# BoomOtter.net
KiCad netlist of a schematic drawn in EAGLE
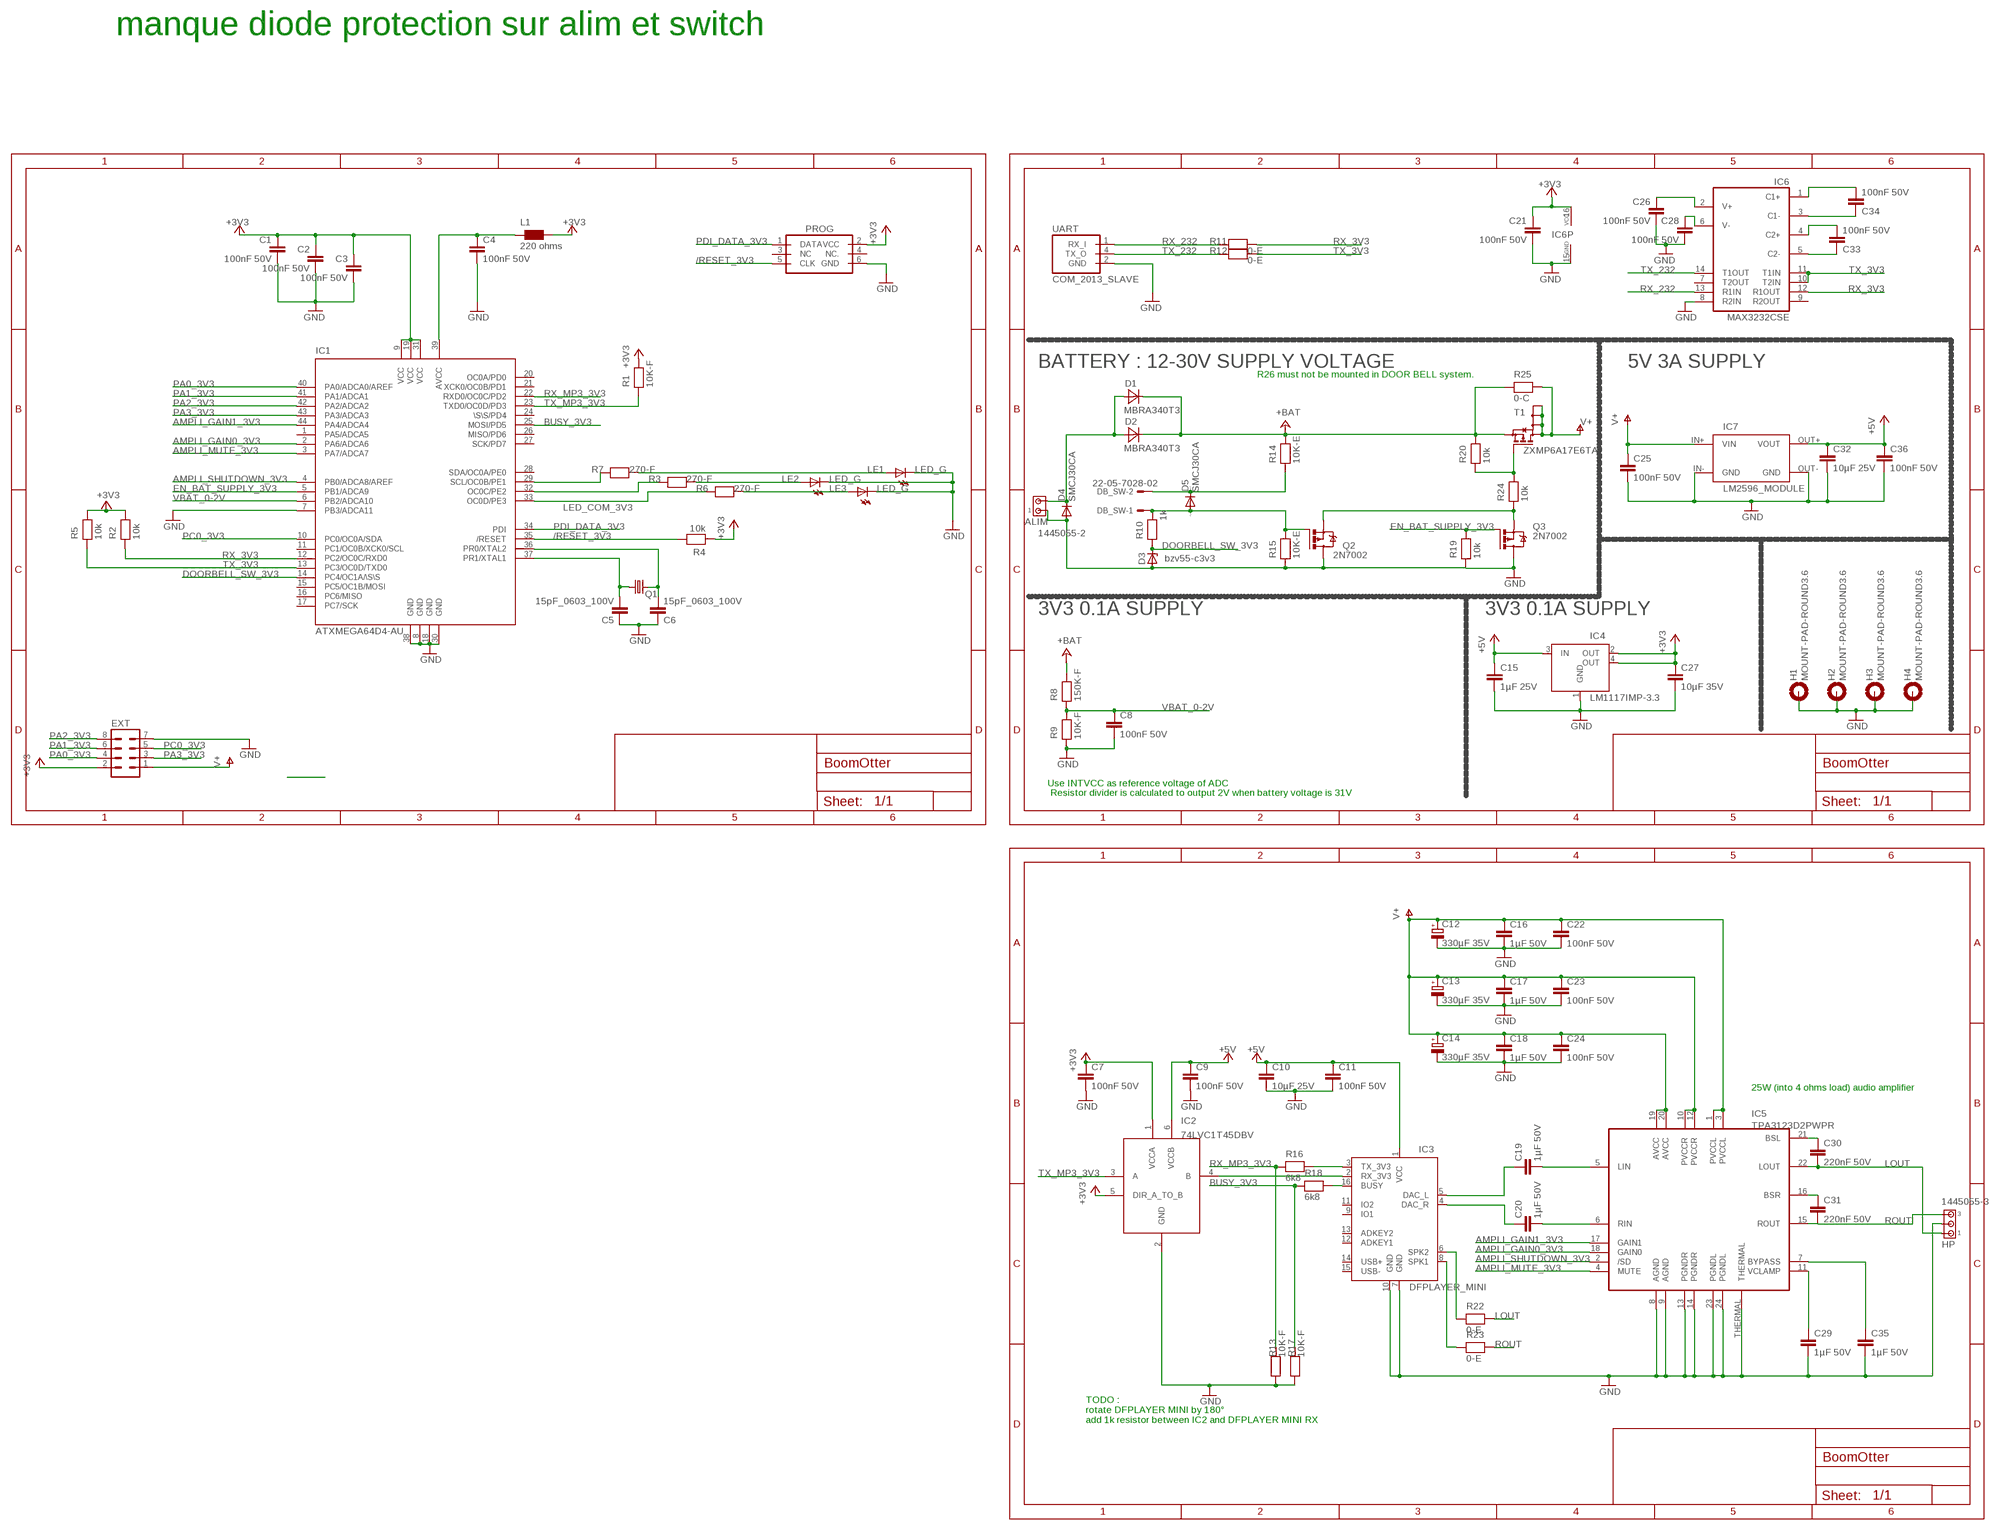
[diagram p0: schematic, sheet 1]

(export (version "E")
  (design (tool "Eeschema 10.0.6"))
  (components
    (comp (ref "ALIM")
      (value "1445055-2")
      (footprint "eagle-import:1445055-2")
      (libsource (lib "eagle-import") (part "1445055-2"))
    )
    (comp (ref "C1")
      (value "100nF 50V")
      (footprint "eagle-import:C0603")
      (libsource (lib "eagle-import") (part "100NF-F"))
    )
    (comp (ref "C2")
      (value "100nF 50V")
      (footprint "eagle-import:C0603")
      (libsource (lib "eagle-import") (part "100NF-F"))
    )
    (comp (ref "C3")
      (value "100nF 50V")
      (footprint "eagle-import:C0603")
      (libsource (lib "eagle-import") (part "100NF-F"))
    )
    (comp (ref "C4")
      (value "100nF 50V")
      (footprint "eagle-import:C0603")
      (libsource (lib "eagle-import") (part "100NF-F"))
    )
    (comp (ref "C5")
      (value "15pF_0603_100V")
      (footprint "eagle-import:C0603")
      (libsource (lib "eagle-import") (part "15PF-F"))
    )
    (comp (ref "C6")
      (value "15pF_0603_100V")
      (footprint "eagle-import:C0603")
      (libsource (lib "eagle-import") (part "15PF-F"))
    )
    (comp (ref "C7")
      (value "100nF 50V")
      (footprint "eagle-import:C0603")
      (libsource (lib "eagle-import") (part "100NF-F"))
    )
    (comp (ref "C8")
      (value "100nF 50V")
      (footprint "eagle-import:C0805")
      (libsource (lib "eagle-import") (part "100NF-E"))
    )
    (comp (ref "C9")
      (value "100nF 50V")
      (footprint "eagle-import:C0603")
      (libsource (lib "eagle-import") (part "100NF-F"))
    )
    (comp (ref "C10")
      (value "10µF 25V")
      (footprint "eagle-import:C1210")
      (libsource (lib "eagle-import") (part "10UF-C_25V"))
    )
    (comp (ref "C11")
      (value "100nF 50V")
      (footprint "eagle-import:C0603")
      (libsource (lib "eagle-import") (part "100NF-F"))
    )
    (comp (ref "C12")
      (value "330µF 35V")
      (footprint "eagle-import:PANASONIC_G")
      (fields (field (name "MANUFACTURER") "EEEFK1V331P"))
      (libsource (lib "eagle-import") (part "330UF"))
    )
    (comp (ref "C13")
      (value "330µF 35V")
      (footprint "eagle-import:PANASONIC_G")
      (fields (field (name "MANUFACTURER") "EEEFK1V331P"))
      (libsource (lib "eagle-import") (part "330UF"))
    )
    (comp (ref "C14")
      (value "330µF 35V")
      (footprint "eagle-import:PANASONIC_G")
      (fields (field (name "MANUFACTURER") "EEEFK1V331P"))
      (libsource (lib "eagle-import") (part "330UF"))
    )
    (comp (ref "C15")
      (value "1µF 25V")
      (footprint "eagle-import:C1206")
      (libsource (lib "eagle-import") (part "1UFD_25V"))
    )
    (comp (ref "C16")
      (value "1µF 50V")
      (footprint "eagle-import:C1206")
      (libsource (lib "eagle-import") (part "1UFD_50V"))
    )
    (comp (ref "C17")
      (value "1µF 50V")
      (footprint "eagle-import:C1206")
      (libsource (lib "eagle-import") (part "1UFD_50V"))
    )
    (comp (ref "C18")
      (value "1µF 50V")
      (footprint "eagle-import:C1206")
      (libsource (lib "eagle-import") (part "1UFD_50V"))
    )
    (comp (ref "C19")
      (value "1µF 50V")
      (footprint "eagle-import:C1206")
      (libsource (lib "eagle-import") (part "1UFD_50V"))
    )
    (comp (ref "C20")
      (value "1µF 50V")
      (footprint "eagle-import:C1206")
      (libsource (lib "eagle-import") (part "1UFD_50V"))
    )
    (comp (ref "C21")
      (value "100nF 50V")
      (footprint "eagle-import:C0603")
      (libsource (lib "eagle-import") (part "100NF-F"))
    )
    (comp (ref "C22")
      (value "100nF 50V")
      (footprint "eagle-import:C0603")
      (libsource (lib "eagle-import") (part "100NF-F"))
    )
    (comp (ref "C23")
      (value "100nF 50V")
      (footprint "eagle-import:C0603")
      (libsource (lib "eagle-import") (part "100NF-F"))
    )
    (comp (ref "C24")
      (value "100nF 50V")
      (footprint "eagle-import:C0603")
      (libsource (lib "eagle-import") (part "100NF-F"))
    )
    (comp (ref "C25")
      (value "100nF 50V")
      (footprint "eagle-import:C0805")
      (libsource (lib "eagle-import") (part "100NF-E"))
    )
    (comp (ref "C26")
      (value "100nF 50V")
      (footprint "eagle-import:C0603")
      (libsource (lib "eagle-import") (part "100NF-F"))
    )
    (comp (ref "C27")
      (value "10µF 35V")
      (footprint "eagle-import:C1210")
      (libsource (lib "eagle-import") (part "10UF-C_35V"))
    )
    (comp (ref "C28")
      (value "100nF 50V")
      (footprint "eagle-import:C0603")
      (libsource (lib "eagle-import") (part "100NF-F"))
    )
    (comp (ref "C29")
      (value "1µF 50V")
      (footprint "eagle-import:C1206")
      (libsource (lib "eagle-import") (part "1UFD_50V"))
    )
    (comp (ref "C30")
      (value "220nF 50V")
      (footprint "eagle-import:C0805")
      (libsource (lib "eagle-import") (part "220NF-F_50V"))
    )
    (comp (ref "C31")
      (value "220nF 50V")
      (footprint "eagle-import:C0805")
      (libsource (lib "eagle-import") (part "220NF-F_50V"))
    )
    (comp (ref "C32")
      (value "10µF 25V")
      (footprint "eagle-import:C1210")
      (libsource (lib "eagle-import") (part "10UF-C_25V"))
    )
    (comp (ref "C33")
      (value "100nF 50V")
      (footprint "eagle-import:C0603")
      (libsource (lib "eagle-import") (part "100NF-F"))
    )
    (comp (ref "C34")
      (value "100nF 50V")
      (footprint "eagle-import:C0603")
      (libsource (lib "eagle-import") (part "100NF-F"))
    )
    (comp (ref "C35")
      (value "1µF 50V")
      (footprint "eagle-import:C1206")
      (libsource (lib "eagle-import") (part "1UFD_50V"))
    )
    (comp (ref "C36")
      (value "100nF 50V")
      (footprint "eagle-import:C0603")
      (libsource (lib "eagle-import") (part "100NF-F"))
    )
    (comp (ref "D1")
      (value "MBRA340T3")
      (footprint "eagle-import:SMA")
      (libsource (lib "eagle-import") (part "MBRA340T3"))
    )
    (comp (ref "D2")
      (value "MBRA340T3")
      (footprint "eagle-import:SMA")
      (libsource (lib "eagle-import") (part "MBRA340T3"))
    )
    (comp (ref "D3")
      (value "bzv55-c3v3")
      (footprint "eagle-import:SOD80C")
      (libsource (lib "eagle-import") (part "BZV55-C3V3SOD80C"))
    )
    (comp (ref "D4")
      (value "SMCJ30CA")
      (footprint "eagle-import:SMC")
      (libsource (lib "eagle-import") (part "DIODE-SMC"))
    )
    (comp (ref "D5")
      (value "SMCJ30CA")
      (footprint "eagle-import:SMC")
      (libsource (lib "eagle-import") (part "DIODE-SMC"))
    )
    (comp (ref "DB_SW")
      (value "22-05-7028-02")
      (footprint "eagle-import:7395-02")
      (libsource (lib "eagle-import") (part "22-?-0205-7028"))
    )
    (comp (ref "EXT")
      (value "MA04-2")
      (footprint "eagle-import:MA04-2")
      (libsource (lib "eagle-import") (part "MA04-2"))
    )
    (comp (ref "H1")
      (value "MOUNT-PAD-ROUND3.6")
      (footprint "eagle-import:3,6-PAD")
      (libsource (lib "eagle-import") (part "MOUNT-PAD-ROUND3.6"))
    )
    (comp (ref "H2")
      (value "MOUNT-PAD-ROUND3.6")
      (footprint "eagle-import:3,6-PAD")
      (libsource (lib "eagle-import") (part "MOUNT-PAD-ROUND3.6"))
    )
    (comp (ref "H3")
      (value "MOUNT-PAD-ROUND3.6")
      (footprint "eagle-import:3,6-PAD")
      (libsource (lib "eagle-import") (part "MOUNT-PAD-ROUND3.6"))
    )
    (comp (ref "H4")
      (value "MOUNT-PAD-ROUND3.6")
      (footprint "eagle-import:3,6-PAD")
      (libsource (lib "eagle-import") (part "MOUNT-PAD-ROUND3.6"))
    )
    (comp (ref "HP")
      (value "1445055-3")
      (footprint "eagle-import:1445055-3")
      (libsource (lib "eagle-import") (part "1445055-3"))
    )
    (comp (ref "IC1")
      (value "ATXMEGA64D4-AU")
      (footprint "eagle-import:TQFP44")
      (libsource (lib "eagle-import") (part "ATXMEGA64D4-AU"))
    )
    (comp (ref "IC2")
      (value "74LVC1T45DBV")
      (footprint "eagle-import:SOT23-6")
      (libsource (lib "eagle-import") (part "74LVC1T45DBV"))
    )
    (comp (ref "IC3")
      (value "DFPLAYER_MINI")
      (footprint "eagle-import:DFPLAYER_MINI")
      (libsource (lib "eagle-import") (part "DFPLAYER_MINI"))
    )
    (comp (ref "IC4")
      (value "LM1117IMP-3.3")
      (footprint "eagle-import:SOT223")
      (libsource (lib "eagle-import") (part "LM1117IMP-3.3"))
    )
    (comp (ref "IC5")
      (value "TPA3123D2PWPR")
      (footprint "eagle-import:HTSSOP24")
      (libsource (lib "eagle-import") (part "TPA3123D2PWPR"))
    )
    (comp (ref "IC6")
      (value "MAX3232CSE")
      (footprint "eagle-import:SO16")
      (libsource (lib "eagle-import") (part "MAX3232SEC"))
    )
    (comp (ref "IC7")
      (value "LM2596_MODULE")
      (footprint "eagle-import:LM2596")
      (libsource (lib "eagle-import") (part "LM2596_MODULE"))
    )
    (comp (ref "L1")
      (value "220 ohms")
      (footprint "eagle-import:R0603")
      (libsource (lib "eagle-import") (part "FERRITE_220OHMS"))
    )
    (comp (ref "LE1")
      (value "LED_G")
      (footprint "eagle-import:CHIP-LED0805")
      (libsource (lib "eagle-import") (part "LED_G"))
    )
    (comp (ref "LE2")
      (value "LED_G")
      (footprint "eagle-import:CHIP-LED0805")
      (libsource (lib "eagle-import") (part "LED_G"))
    )
    (comp (ref "LE3")
      (value "LED_G")
      (footprint "eagle-import:CHIP-LED0805")
      (libsource (lib "eagle-import") (part "LED_G"))
    )
    (comp (ref "PROG")
      (value "PDI_ATMELL")
      (footprint "eagle-import:ML6L")
      (libsource (lib "eagle-import") (part "PDI_ATMELL"))
    )
    (comp (ref "Q1")
      (value "CRYSTAL_16MHZ_5032")
      (footprint "eagle-import:CRYSTAL_5032")
      (libsource (lib "eagle-import") (part "CRYSTAL_16MHZ_5032"))
    )
    (comp (ref "Q2")
      (value "2N7002")
      (footprint "eagle-import:SOT23")
      (libsource (lib "eagle-import") (part "2N7002"))
    )
    (comp (ref "Q3")
      (value "2N7002")
      (footprint "eagle-import:SOT23")
      (libsource (lib "eagle-import") (part "2N7002"))
    )
    (comp (ref "R1")
      (value "10K-F")
      (footprint "eagle-import:R0603")
      (libsource (lib "eagle-import") (part "10K-F"))
    )
    (comp (ref "R2")
      (value "10k")
      (footprint "eagle-import:R0603")
      (libsource (lib "eagle-import") (part "10K-F"))
    )
    (comp (ref "R3")
      (value "270-F")
      (footprint "eagle-import:R0603")
      (libsource (lib "eagle-import") (part "270-F"))
    )
    (comp (ref "R4")
      (value "10k")
      (footprint "eagle-import:R0603")
      (libsource (lib "eagle-import") (part "10K-F"))
    )
    (comp (ref "R5")
      (value "10k")
      (footprint "eagle-import:R0603")
      (libsource (lib "eagle-import") (part "10K-F"))
    )
    (comp (ref "R6")
      (value "270-F")
      (footprint "eagle-import:R0603")
      (libsource (lib "eagle-import") (part "270-F"))
    )
    (comp (ref "R7")
      (value "270-F")
      (footprint "eagle-import:R0603")
      (libsource (lib "eagle-import") (part "270-F"))
    )
    (comp (ref "R8")
      (value "150K-F")
      (footprint "eagle-import:R0603")
      (libsource (lib "eagle-import") (part "150K-F"))
    )
    (comp (ref "R9")
      (value "10K-F")
      (footprint "eagle-import:R0603")
      (libsource (lib "eagle-import") (part "10K-F"))
    )
    (comp (ref "R10")
      (value "1k")
      (footprint "eagle-import:R0603")
      (libsource (lib "eagle-import") (part "1K-F"))
    )
    (comp (ref "R11")
      (value "0-E")
      (footprint "eagle-import:R0805")
      (libsource (lib "eagle-import") (part "0-E"))
    )
    (comp (ref "R12")
      (value "0-E")
      (footprint "eagle-import:R0805")
      (libsource (lib "eagle-import") (part "0-E"))
    )
    (comp (ref "R13")
      (value "10K-F")
      (footprint "eagle-import:R0603")
      (libsource (lib "eagle-import") (part "10K-F"))
    )
    (comp (ref "R14")
      (value "10K-E")
      (footprint "eagle-import:R0805")
      (libsource (lib "eagle-import") (part "10K-E"))
    )
    (comp (ref "R15")
      (value "10K-E")
      (footprint "eagle-import:R0805")
      (libsource (lib "eagle-import") (part "10K-E"))
    )
    (comp (ref "R16")
      (value "6k8")
      (footprint "eagle-import:R0603")
      (libsource (lib "eagle-import") (part "6K8-F"))
    )
    (comp (ref "R17")
      (value "10K-F")
      (footprint "eagle-import:R0603")
      (libsource (lib "eagle-import") (part "10K-F"))
    )
    (comp (ref "R18")
      (value "6k8")
      (footprint "eagle-import:R0603")
      (libsource (lib "eagle-import") (part "6K8-F"))
    )
    (comp (ref "R19")
      (value "10k")
      (footprint "eagle-import:R0603")
      (libsource (lib "eagle-import") (part "10K-F"))
    )
    (comp (ref "R20")
      (value "10k")
      (footprint "eagle-import:R0603")
      (libsource (lib "eagle-import") (part "10K-F"))
    )
    (comp (ref "R22")
      (value "0-E")
      (footprint "eagle-import:R0805")
      (libsource (lib "eagle-import") (part "0-E"))
    )
    (comp (ref "R23")
      (value "0-E")
      (footprint "eagle-import:R0805")
      (libsource (lib "eagle-import") (part "0-E"))
    )
    (comp (ref "R24")
      (value "10k")
      (footprint "eagle-import:R0603")
      (libsource (lib "eagle-import") (part "10K-F"))
    )
    (comp (ref "R25")
      (value "0-C")
      (footprint "eagle-import:R1210")
      (libsource (lib "eagle-import") (part "0-C"))
    )
    (comp (ref "T1")
      (value "ZXMP6A17E6TA")
      (footprint "eagle-import:SOT26")
      (libsource (lib "eagle-import") (part "ZXMP6A17E6TA"))
    )
    (comp (ref "UART")
      (value "COM_2013_SLAVE")
      (footprint "eagle-import:MICROMATCH-4_SMD")
      (libsource (lib "eagle-import") (part "COM_2013_SLAVE"))
    )
  )
  (nets
    (net (code "1") (name "+3V3") (class "Default")
      (node (ref "C1") (pin "1") (pinfunction "1_1") (pintype "passive"))
      (node (ref "C2") (pin "1") (pinfunction "1_1") (pintype "passive"))
      (node (ref "C21") (pin "1") (pinfunction "1_1") (pintype "passive"))
      (node (ref "C27") (pin "1") (pinfunction "1_1") (pintype "passive"))
      (node (ref "C3") (pin "1") (pinfunction "1_1") (pintype "passive"))
      (node (ref "C7") (pin "1") (pinfunction "1_1") (pintype "passive"))
      (node (ref "EXT") (pin "2") (pinfunction "2_2") (pintype "passive"))
      (node (ref "IC1") (pin "19") (pinfunction "VCC_19") (pintype "bidirectional"))
      (node (ref "IC1") (pin "31") (pinfunction "VCC_31") (pintype "bidirectional"))
      (node (ref "IC1") (pin "9") (pinfunction "VCC_9") (pintype "bidirectional"))
      (node (ref "IC2") (pin "1") (pinfunction "VCCA_1") (pintype "power_in"))
      (node (ref "IC2") (pin "5") (pinfunction "DIR_A_TO_B_5") (pintype "bidirectional"))
      (node (ref "IC4") (pin "2") (pinfunction "OUT_2") (pintype "bidirectional"))
      (node (ref "IC4") (pin "4") (pinfunction "OUT_4") (pintype "bidirectional"))
      (node (ref "IC6") (pin "16") (pinfunction "VCC_16") (pintype "power_in"))
      (node (ref "L1") (pin "2") (pinfunction "2_2") (pintype "passive"))
      (node (ref "PROG") (pin "2") (pinfunction "VCC_2") (pintype "passive"))
      (node (ref "R1") (pin "2") (pinfunction "2_2") (pintype "bidirectional"))
      (node (ref "R2") (pin "2") (pinfunction "2_2") (pintype "bidirectional"))
      (node (ref "R4") (pin "1") (pinfunction "1_1") (pintype "bidirectional"))
      (node (ref "R5") (pin "2") (pinfunction "2_2") (pintype "bidirectional"))
    )
    (net (code "2") (name "+5V") (class "Default")
      (node (ref "C10") (pin "1") (pinfunction "1_1") (pintype "passive"))
      (node (ref "C11") (pin "1") (pinfunction "1_1") (pintype "passive"))
      (node (ref "C15") (pin "1") (pinfunction "1_1") (pintype "passive"))
      (node (ref "C32") (pin "1") (pinfunction "1_1") (pintype "passive"))
      (node (ref "C36") (pin "1") (pinfunction "1_1") (pintype "passive"))
      (node (ref "C9") (pin "1") (pinfunction "1_1") (pintype "passive"))
      (node (ref "IC2") (pin "6") (pinfunction "VCCB_6") (pintype "power_in"))
      (node (ref "IC3") (pin "1") (pinfunction "VCC_1") (pintype "power_in"))
      (node (ref "IC4") (pin "3") (pinfunction "IN_3") (pintype "bidirectional"))
      (node (ref "IC7") (pin "OUT+") (pinfunction "VOUT_OUT+") (pintype "bidirectional"))
    )
    (net (code "3") (name "+BAT") (class "Default")
      (node (ref "D1") (pin "C") (pinfunction "C_C") (pintype "passive"))
      (node (ref "D2") (pin "C") (pinfunction "C_C") (pintype "passive"))
      (node (ref "R14") (pin "2") (pinfunction "2_2") (pintype "bidirectional"))
      (node (ref "R20") (pin "2") (pinfunction "2_2") (pintype "bidirectional"))
      (node (ref "R25") (pin "1") (pinfunction "1_1") (pintype "bidirectional"))
      (node (ref "R8") (pin "2") (pinfunction "2_2") (pintype "bidirectional"))
      (node (ref "T1") (pin "4") (pinfunction "S_4") (pintype "passive"))
    )
    (net (code "4") (name "/AMPLI_GAIN0_3V3") (class "Default")
      (node (ref "IC1") (pin "2") (pinfunction "PA6/ADCA6_2") (pintype "bidirectional"))
      (node (ref "IC5") (pin "18") (pinfunction "GAIN0_18") (pintype "input"))
    )
    (net (code "5") (name "/AMPLI_GAIN1_3V3") (class "Default")
      (node (ref "IC1") (pin "44") (pinfunction "PA4/ADCA4_44") (pintype "bidirectional"))
      (node (ref "IC5") (pin "17") (pinfunction "GAIN1_17") (pintype "input"))
    )
    (net (code "6") (name "/AMPLI_MUTE_3V3") (class "Default")
      (node (ref "IC1") (pin "3") (pinfunction "PA7/ADCA7_3") (pintype "bidirectional"))
      (node (ref "IC5") (pin "4") (pinfunction "MUTE_4") (pintype "input"))
    )
    (net (code "7") (name "/AMPLI_SHUTDOWN_3V3") (class "Default")
      (node (ref "IC1") (pin "4") (pinfunction "PB0/ADCA8/AREF_4") (pintype "bidirectional"))
      (node (ref "IC5") (pin "2") (pinfunction "/SD_2") (pintype "input"))
    )
    (net (code "8") (name "/BUSY_3V3") (class "Default")
      (node (ref "IC1") (pin "25") (pinfunction "MOSI/PD5_25") (pintype "bidirectional"))
      (node (ref "R17") (pin "2") (pinfunction "2_2") (pintype "bidirectional"))
      (node (ref "R18") (pin "1") (pinfunction "1_1") (pintype "bidirectional"))
    )
    (net (code "9") (name "/DOORBELL_SW_3V3") (class "Default")
      (node (ref "D3") (pin "C") (pinfunction "C_C") (pintype "passive"))
      (node (ref "IC1") (pin "14") (pinfunction "PC4/OC1A/\\S\\S_14") (pintype "bidirectional"))
      (node (ref "R10") (pin "1") (pinfunction "1_1") (pintype "bidirectional"))
    )
    (net (code "10") (name "/EN_BAT_SUPPLY_3V3") (class "Default")
      (node (ref "IC1") (pin "5") (pinfunction "PB1/ADCA9_5") (pintype "bidirectional"))
      (node (ref "Q3") (pin "1") (pinfunction "G_1") (pintype "passive"))
      (node (ref "R19") (pin "2") (pinfunction "2_2") (pintype "bidirectional"))
    )
    (net (code "11") (name "/LED_COM_3V3") (class "Default")
      (node (ref "IC1") (pin "29") (pinfunction "SCL/OC0B/PE1_29") (pintype "bidirectional"))
      (node (ref "R7") (pin "1") (pinfunction "1_1") (pintype "bidirectional"))
    )
    (net (code "12") (name "/LOUT") (class "Default")
      (node (ref "C30") (pin "2") (pinfunction "2_2") (pintype "passive"))
      (node (ref "HP") (pin "1") (pinfunction "1_1") (pintype "passive"))
      (node (ref "IC5") (pin "22") (pinfunction "LOUT_22") (pintype "output"))
      (node (ref "R22") (pin "2") (pinfunction "2_2") (pintype "bidirectional"))
    )
    (net (code "13") (name "/PA0_3V3") (class "Default")
      (node (ref "EXT") (pin "4") (pinfunction "4_4") (pintype "passive"))
      (node (ref "IC1") (pin "40") (pinfunction "PA0/ADCA0/AREF_40") (pintype "bidirectional"))
    )
    (net (code "14") (name "/PA1_3V3") (class "Default")
      (node (ref "EXT") (pin "6") (pinfunction "6_6") (pintype "passive"))
      (node (ref "IC1") (pin "41") (pinfunction "PA1/ADCA1_41") (pintype "bidirectional"))
    )
    (net (code "15") (name "/PA2_3V3") (class "Default")
      (node (ref "EXT") (pin "8") (pinfunction "8_8") (pintype "passive"))
      (node (ref "IC1") (pin "42") (pinfunction "PA2/ADCA2_42") (pintype "bidirectional"))
    )
    (net (code "16") (name "/PA3_3V3") (class "Default")
      (node (ref "EXT") (pin "3") (pinfunction "3_3") (pintype "passive"))
      (node (ref "IC1") (pin "43") (pinfunction "PA3/ADCA3_43") (pintype "bidirectional"))
    )
    (net (code "17") (name "/PC0_3V3") (class "Default")
      (node (ref "EXT") (pin "5") (pinfunction "5_5") (pintype "passive"))
      (node (ref "IC1") (pin "10") (pinfunction "PC0/OC0A/SDA_10") (pintype "bidirectional"))
    )
    (net (code "18") (name "/PDI_DATA_3V3") (class "Default")
      (node (ref "IC1") (pin "34") (pinfunction "PDI_34") (pintype "bidirectional"))
      (node (ref "PROG") (pin "1") (pinfunction "DATA_1") (pintype "passive"))
    )
    (net (code "19") (name "/ROUT") (class "Default")
      (node (ref "C31") (pin "2") (pinfunction "2_2") (pintype "passive"))
      (node (ref "HP") (pin "3") (pinfunction "3_3") (pintype "passive"))
      (node (ref "IC5") (pin "15") (pinfunction "ROUT_15") (pintype "output"))
      (node (ref "R23") (pin "2") (pinfunction "2_2") (pintype "bidirectional"))
    )
    (net (code "20") (name "/RX_3V3") (class "Default")
      (node (ref "IC1") (pin "12") (pinfunction "PC2/OC0C/RXD0_12") (pintype "bidirectional"))
      (node (ref "IC6") (pin "12") (pinfunction "R1OUT_12") (pintype "output"))
      (node (ref "R11") (pin "2") (pinfunction "2_2") (pintype "bidirectional"))
      (node (ref "R2") (pin "1") (pinfunction "1_1") (pintype "bidirectional"))
    )
    (net (code "21") (name "/RX_232") (class "Default")
      (node (ref "IC6") (pin "13") (pinfunction "R1IN_13") (pintype "input"))
      (node (ref "R11") (pin "1") (pinfunction "1_1") (pintype "bidirectional"))
      (node (ref "UART") (pin "1") (pinfunction "RX_I_1") (pintype "passive"))
    )
    (net (code "22") (name "/RX_MP3_3V3") (class "Default")
      (node (ref "IC1") (pin "22") (pinfunction "RXD0/OC0C/PD2_22") (pintype "bidirectional"))
      (node (ref "R13") (pin "2") (pinfunction "2_2") (pintype "bidirectional"))
      (node (ref "R16") (pin "1") (pinfunction "1_1") (pintype "bidirectional"))
    )
    (net (code "23") (name "/TX_3V3") (class "Default")
      (node (ref "IC1") (pin "13") (pinfunction "PC3/OC0D/TXD0_13") (pintype "bidirectional"))
      (node (ref "IC6") (pin "10") (pinfunction "T2IN_10") (pintype "input"))
      (node (ref "IC6") (pin "11") (pinfunction "T1IN_11") (pintype "input"))
      (node (ref "R12") (pin "2") (pinfunction "2_2") (pintype "bidirectional"))
      (node (ref "R5") (pin "1") (pinfunction "1_1") (pintype "bidirectional"))
    )
    (net (code "24") (name "/TX_232") (class "Default")
      (node (ref "IC6") (pin "14") (pinfunction "T1OUT_14") (pintype "output"))
      (node (ref "R12") (pin "1") (pinfunction "1_1") (pintype "bidirectional"))
      (node (ref "UART") (pin "4") (pinfunction "TX_O_4") (pintype "passive"))
    )
    (net (code "25") (name "/TX_MP3_3V3") (class "Default")
      (node (ref "IC1") (pin "23") (pinfunction "TXD0/OC0D/PD3_23") (pintype "bidirectional"))
      (node (ref "IC2") (pin "3") (pinfunction "A_3") (pintype "bidirectional"))
      (node (ref "R1") (pin "1") (pinfunction "1_1") (pintype "bidirectional"))
    )
    (net (code "26") (name "/VBAT_0-2V") (class "Default")
      (node (ref "C8") (pin "1") (pinfunction "1_1") (pintype "passive"))
      (node (ref "IC1") (pin "6") (pinfunction "PB2/ADCA10_6") (pintype "bidirectional"))
      (node (ref "R8") (pin "1") (pinfunction "1_1") (pintype "bidirectional"))
      (node (ref "R9") (pin "2") (pinfunction "2_2") (pintype "bidirectional"))
    )
    (net (code "27") (name "/{slash}RESET_3V3") (class "Default")
      (node (ref "IC1") (pin "35") (pinfunction "/RESET_35") (pintype "bidirectional"))
      (node (ref "PROG") (pin "5") (pinfunction "CLK_5") (pintype "passive"))
      (node (ref "R4") (pin "2") (pinfunction "2_2") (pintype "bidirectional"))
    )
    (net (code "28") (name "GND") (class "Default")
      (node (ref "ALIM") (pin "1") (pinfunction "1_1") (pintype "passive"))
      (node (ref "C1") (pin "2") (pinfunction "2_2") (pintype "passive"))
      (node (ref "C10") (pin "2") (pinfunction "2_2") (pintype "passive"))
      (node (ref "C11") (pin "2") (pinfunction "2_2") (pintype "passive"))
      (node (ref "C12") (pin "-") (pinfunction "-_-") (pintype "passive"))
      (node (ref "C13") (pin "-") (pinfunction "-_-") (pintype "passive"))
      (node (ref "C14") (pin "-") (pinfunction "-_-") (pintype "passive"))
      (node (ref "C15") (pin "2") (pinfunction "2_2") (pintype "passive"))
      (node (ref "C16") (pin "2") (pinfunction "2_2") (pintype "passive"))
      (node (ref "C17") (pin "2") (pinfunction "2_2") (pintype "passive"))
      (node (ref "C18") (pin "2") (pinfunction "2_2") (pintype "passive"))
      (node (ref "C2") (pin "2") (pinfunction "2_2") (pintype "passive"))
      (node (ref "C21") (pin "2") (pinfunction "2_2") (pintype "passive"))
      (node (ref "C22") (pin "2") (pinfunction "2_2") (pintype "passive"))
      (node (ref "C23") (pin "2") (pinfunction "2_2") (pintype "passive"))
      (node (ref "C24") (pin "2") (pinfunction "2_2") (pintype "passive"))
      (node (ref "C25") (pin "2") (pinfunction "2_2") (pintype "passive"))
      (node (ref "C26") (pin "2") (pinfunction "2_2") (pintype "passive"))
      (node (ref "C27") (pin "2") (pinfunction "2_2") (pintype "passive"))
      (node (ref "C28") (pin "2") (pinfunction "2_2") (pintype "passive"))
      (node (ref "C29") (pin "2") (pinfunction "2_2") (pintype "passive"))
      (node (ref "C3") (pin "2") (pinfunction "2_2") (pintype "passive"))
      (node (ref "C32") (pin "2") (pinfunction "2_2") (pintype "passive"))
      (node (ref "C35") (pin "2") (pinfunction "2_2") (pintype "passive"))
      (node (ref "C36") (pin "2") (pinfunction "2_2") (pintype "passive"))
      (node (ref "C4") (pin "2") (pinfunction "2_2") (pintype "passive"))
      (node (ref "C5") (pin "1") (pinfunction "1_1") (pintype "passive"))
      (node (ref "C6") (pin "1") (pinfunction "1_1") (pintype "passive"))
      (node (ref "C7") (pin "2") (pinfunction "2_2") (pintype "passive"))
      (node (ref "C8") (pin "2") (pinfunction "2_2") (pintype "passive"))
      (node (ref "C9") (pin "2") (pinfunction "2_2") (pintype "passive"))
      (node (ref "D3") (pin "A") (pinfunction "A_A") (pintype "passive"))
      (node (ref "D4") (pin "A") (pinfunction "A_A") (pintype "passive"))
      (node (ref "EXT") (pin "7") (pinfunction "7_7") (pintype "passive"))
      (node (ref "H1") (pin "B3,6") (pinfunction "MOUNT_B3,6") (pintype "passive"))
      (node (ref "H2") (pin "B3,6") (pinfunction "MOUNT_B3,6") (pintype "passive"))
      (node (ref "H3") (pin "B3,6") (pinfunction "MOUNT_B3,6") (pintype "passive"))
      (node (ref "H4") (pin "B3,6") (pinfunction "MOUNT_B3,6") (pintype "passive"))
      (node (ref "HP") (pin "2") (pinfunction "2_2") (pintype "passive"))
      (node (ref "IC1") (pin "18") (pinfunction "GND_18") (pintype "bidirectional"))
      (node (ref "IC1") (pin "30") (pinfunction "GND_30") (pintype "bidirectional"))
      (node (ref "IC1") (pin "38") (pinfunction "GND_38") (pintype "bidirectional"))
      (node (ref "IC1") (pin "7") (pinfunction "PB3/ADCA11_7") (pintype "bidirectional"))
      (node (ref "IC1") (pin "8") (pinfunction "GND_8") (pintype "bidirectional"))
      (node (ref "IC2") (pin "2") (pinfunction "GND_2") (pintype "power_in"))
      (node (ref "IC3") (pin "10") (pinfunction "GND_10") (pintype "power_in"))
      (node (ref "IC3") (pin "7") (pinfunction "GND_7") (pintype "power_in"))
      (node (ref "IC4") (pin "1") (pinfunction "GND_1") (pintype "bidirectional"))
      (node (ref "IC5") (pin "13") (pinfunction "PGNDR_13") (pintype "power_in"))
      (node (ref "IC5") (pin "14") (pinfunction "PGNDR_14") (pintype "power_in"))
      (node (ref "IC5") (pin "23") (pinfunction "PGNDL_23") (pintype "power_in"))
      (node (ref "IC5") (pin "24") (pinfunction "PGNDL_24") (pintype "power_in"))
      (node (ref "IC5") (pin "8") (pinfunction "AGND_8") (pintype "power_in"))
      (node (ref "IC5") (pin "9") (pinfunction "AGND_9") (pintype "power_in"))
      (node (ref "IC5") (pin "THERMAL") (pinfunction "THERMAL_THERMAL") (pintype "power_in"))
      (node (ref "IC6") (pin "15") (pinfunction "GND_15") (pintype "power_in"))
      (node (ref "IC6") (pin "8") (pinfunction "R2IN_8") (pintype "input"))
      (node (ref "IC7") (pin "IN-") (pinfunction "GND_IN-") (pintype "bidirectional"))
      (node (ref "IC7") (pin "OUT-") (pinfunction "GND_OUT-") (pintype "bidirectional"))
      (node (ref "LE1") (pin "C") (pinfunction "C_C") (pintype "passive"))
      (node (ref "LE2") (pin "C") (pinfunction "C_C") (pintype "passive"))
      (node (ref "LE3") (pin "C") (pinfunction "C_C") (pintype "passive"))
      (node (ref "PROG") (pin "6") (pinfunction "GND_6") (pintype "passive"))
      (node (ref "Q2") (pin "2") (pinfunction "D_2") (pintype "passive"))
      (node (ref "Q3") (pin "2") (pinfunction "D_2") (pintype "passive"))
      (node (ref "R13") (pin "1") (pinfunction "1_1") (pintype "bidirectional"))
      (node (ref "R15") (pin "1") (pinfunction "1_1") (pintype "bidirectional"))
      (node (ref "R17") (pin "1") (pinfunction "1_1") (pintype "bidirectional"))
      (node (ref "R19") (pin "1") (pinfunction "1_1") (pintype "bidirectional"))
      (node (ref "R9") (pin "1") (pinfunction "1_1") (pintype "bidirectional"))
      (node (ref "UART") (pin "2") (pinfunction "GND_2") (pintype "passive"))
    )
    (net (code "29") (name "Net-(ALIM-Pad2)") (class "Default")
      (node (ref "ALIM") (pin "2") (pinfunction "2_2") (pintype "passive"))
      (node (ref "D1") (pin "A") (pinfunction "A_A") (pintype "passive"))
      (node (ref "D2") (pin "A") (pinfunction "A_A") (pintype "passive"))
      (node (ref "D4") (pin "C") (pinfunction "C_C") (pintype "passive"))
    )
    (net (code "30") (name "Net-(DB_SWA-S)") (class "Default")
      (node (ref "D5") (pin "A") (pinfunction "A_A") (pintype "passive"))
      (node (ref "DB_SW") (pin "1") (pinfunction "S_1") (pintype "passive"))
      (node (ref "Q2") (pin "1") (pinfunction "G_1") (pintype "passive"))
      (node (ref "R10") (pin "2") (pinfunction "2_2") (pintype "bidirectional"))
      (node (ref "R15") (pin "2") (pinfunction "2_2") (pintype "bidirectional"))
    )
    (net (code "31") (name "Net-(DB_SWB-S)") (class "Default")
      (node (ref "D5") (pin "C") (pinfunction "C_C") (pintype "passive"))
      (node (ref "DB_SW") (pin "2") (pinfunction "S_2") (pintype "passive"))
      (node (ref "R14") (pin "1") (pinfunction "1_1") (pintype "bidirectional"))
    )
    (net (code "32") (name "Net-(IC1-AVCC)") (class "Default")
      (node (ref "C4") (pin "1") (pinfunction "1_1") (pintype "passive"))
      (node (ref "IC1") (pin "39") (pinfunction "AVCC_39") (pintype "bidirectional"))
      (node (ref "L1") (pin "1") (pinfunction "1_1") (pintype "passive"))
    )
    (net (code "33") (name "Net-(IC1-OC0C{slash}PE2)") (class "Default")
      (node (ref "IC1") (pin "32") (pinfunction "OC0C/PE2_32") (pintype "bidirectional"))
      (node (ref "R3") (pin "1") (pinfunction "1_1") (pintype "bidirectional"))
    )
    (net (code "34") (name "Net-(IC1-OC0D{slash}PE3)") (class "Default")
      (node (ref "IC1") (pin "33") (pinfunction "OC0D/PE3_33") (pintype "bidirectional"))
      (node (ref "R6") (pin "1") (pinfunction "1_1") (pintype "bidirectional"))
    )
    (net (code "35") (name "Net-(IC1-PR0{slash}XTAL2)") (class "Default")
      (node (ref "C6") (pin "2") (pinfunction "2_2") (pintype "passive"))
      (node (ref "IC1") (pin "36") (pinfunction "PR0/XTAL2_36") (pintype "bidirectional"))
      (node (ref "Q1") (pin "2") (pinfunction "2_2") (pintype "passive"))
    )
    (net (code "36") (name "Net-(IC1-PR1{slash}XTAL1)") (class "Default")
      (node (ref "C5") (pin "2") (pinfunction "2_2") (pintype "passive"))
      (node (ref "IC1") (pin "37") (pinfunction "PR1/XTAL1_37") (pintype "bidirectional"))
      (node (ref "Q1") (pin "1") (pinfunction "1_1") (pintype "passive"))
    )
    (net (code "37") (name "Net-(IC2-B)") (class "Default")
      (node (ref "IC2") (pin "4") (pinfunction "B_4") (pintype "bidirectional"))
      (node (ref "IC3") (pin "2") (pinfunction "RX_3V3_2") (pintype "input"))
    )
    (net (code "38") (name "Net-(IC3-BUSY)") (class "Default")
      (node (ref "IC3") (pin "16") (pinfunction "BUSY_16") (pintype "bidirectional"))
      (node (ref "R18") (pin "2") (pinfunction "2_2") (pintype "bidirectional"))
    )
    (net (code "39") (name "Net-(IC3-DAC_L)") (class "Default")
      (node (ref "C19") (pin "1") (pinfunction "1_1") (pintype "passive"))
      (node (ref "IC3") (pin "5") (pinfunction "DAC_L_5") (pintype "output"))
    )
    (net (code "40") (name "Net-(IC3-DAC_R)") (class "Default")
      (node (ref "C20") (pin "1") (pinfunction "1_1") (pintype "passive"))
      (node (ref "IC3") (pin "4") (pinfunction "DAC_R_4") (pintype "output"))
    )
    (net (code "41") (name "Net-(IC3-SPK1)") (class "Default")
      (node (ref "IC3") (pin "8") (pinfunction "SPK1_8") (pintype "power_in"))
      (node (ref "R23") (pin "1") (pinfunction "1_1") (pintype "bidirectional"))
    )
    (net (code "42") (name "Net-(IC3-SPK2)") (class "Default")
      (node (ref "IC3") (pin "6") (pinfunction "SPK2_6") (pintype "power_in"))
      (node (ref "R22") (pin "1") (pinfunction "1_1") (pintype "bidirectional"))
    )
    (net (code "43") (name "Net-(IC3-TX_3V3)") (class "Default")
      (node (ref "IC3") (pin "3") (pinfunction "TX_3V3_3") (pintype "output"))
      (node (ref "R16") (pin "2") (pinfunction "2_2") (pintype "bidirectional"))
    )
    (net (code "44") (name "Net-(IC5-BSL)") (class "Default")
      (node (ref "C30") (pin "1") (pinfunction "1_1") (pintype "passive"))
      (node (ref "IC5") (pin "21") (pinfunction "BSL_21") (pintype "bidirectional"))
    )
    (net (code "45") (name "Net-(IC5-BSR)") (class "Default")
      (node (ref "C31") (pin "1") (pinfunction "1_1") (pintype "passive"))
      (node (ref "IC5") (pin "16") (pinfunction "BSR_16") (pintype "bidirectional"))
    )
    (net (code "46") (name "Net-(IC5-BYPASS)") (class "Default")
      (node (ref "C35") (pin "1") (pinfunction "1_1") (pintype "passive"))
      (node (ref "IC5") (pin "7") (pinfunction "BYPASS_7") (pintype "output"))
    )
    (net (code "47") (name "Net-(IC5-LIN)") (class "Default")
      (node (ref "C19") (pin "2") (pinfunction "2_2") (pintype "passive"))
      (node (ref "IC5") (pin "5") (pinfunction "LIN_5") (pintype "input"))
    )
    (net (code "48") (name "Net-(IC5-RIN)") (class "Default")
      (node (ref "C20") (pin "2") (pinfunction "2_2") (pintype "passive"))
      (node (ref "IC5") (pin "6") (pinfunction "RIN_6") (pintype "input"))
    )
    (net (code "49") (name "Net-(IC5-VCLAMP)") (class "Default")
      (node (ref "C29") (pin "1") (pinfunction "1_1") (pintype "passive"))
      (node (ref "IC5") (pin "11") (pinfunction "VCLAMP_11") (pintype "power_in"))
    )
    (net (code "50") (name "Net-(IC6A-C1+)") (class "Default")
      (node (ref "C34") (pin "1") (pinfunction "1_1") (pintype "passive"))
      (node (ref "IC6") (pin "1") (pinfunction "C1+_1") (pintype "bidirectional"))
    )
    (net (code "51") (name "Net-(IC6A-C1-)") (class "Default")
      (node (ref "C34") (pin "2") (pinfunction "2_2") (pintype "passive"))
      (node (ref "IC6") (pin "3") (pinfunction "C1-_3") (pintype "bidirectional"))
    )
    (net (code "52") (name "Net-(IC6A-C2+)") (class "Default")
      (node (ref "C33") (pin "1") (pinfunction "1_1") (pintype "passive"))
      (node (ref "IC6") (pin "4") (pinfunction "C2+_4") (pintype "bidirectional"))
    )
    (net (code "53") (name "Net-(IC6A-C2-)") (class "Default")
      (node (ref "C33") (pin "2") (pinfunction "2_2") (pintype "passive"))
      (node (ref "IC6") (pin "5") (pinfunction "C2-_5") (pintype "bidirectional"))
    )
    (net (code "54") (name "Net-(IC6A-V+)") (class "Default")
      (node (ref "C26") (pin "1") (pinfunction "1_1") (pintype "passive"))
      (node (ref "IC6") (pin "2") (pinfunction "V+_2") (pintype "bidirectional"))
    )
    (net (code "55") (name "Net-(IC6A-V-)") (class "Default")
      (node (ref "C28") (pin "1") (pinfunction "1_1") (pintype "passive"))
      (node (ref "IC6") (pin "6") (pinfunction "V-_6") (pintype "bidirectional"))
    )
    (net (code "56") (name "Net-(LE1-PadA)") (class "Default")
      (node (ref "LE1") (pin "A") (pinfunction "A_A") (pintype "passive"))
      (node (ref "R7") (pin "2") (pinfunction "2_2") (pintype "bidirectional"))
    )
    (net (code "57") (name "Net-(LE2-PadA)") (class "Default")
      (node (ref "LE2") (pin "A") (pinfunction "A_A") (pintype "passive"))
      (node (ref "R3") (pin "2") (pinfunction "2_2") (pintype "bidirectional"))
    )
    (net (code "58") (name "Net-(LE3-PadA)") (class "Default")
      (node (ref "LE3") (pin "A") (pinfunction "A_A") (pintype "passive"))
      (node (ref "R6") (pin "2") (pinfunction "2_2") (pintype "bidirectional"))
    )
    (net (code "59") (name "Net-(Q2-S)") (class "Default")
      (node (ref "Q2") (pin "3") (pinfunction "S_3") (pintype "passive"))
      (node (ref "Q3") (pin "3") (pinfunction "S_3") (pintype "passive"))
      (node (ref "R24") (pin "1") (pinfunction "1_1") (pintype "bidirectional"))
    )
    (net (code "60") (name "Net-(T1-G)") (class "Default")
      (node (ref "R20") (pin "1") (pinfunction "1_1") (pintype "bidirectional"))
      (node (ref "R24") (pin "2") (pinfunction "2_2") (pintype "bidirectional"))
      (node (ref "T1") (pin "3") (pinfunction "G_3") (pintype "passive"))
    )
    (net (code "61") (name "V+") (class "Default")
      (node (ref "C12") (pin "+") (pinfunction "+_+") (pintype "passive"))
      (node (ref "C13") (pin "+") (pinfunction "+_+") (pintype "passive"))
      (node (ref "C14") (pin "+") (pinfunction "+_+") (pintype "passive"))
      (node (ref "C16") (pin "1") (pinfunction "1_1") (pintype "passive"))
      (node (ref "C17") (pin "1") (pinfunction "1_1") (pintype "passive"))
      (node (ref "C18") (pin "1") (pinfunction "1_1") (pintype "passive"))
      (node (ref "C22") (pin "1") (pinfunction "1_1") (pintype "passive"))
      (node (ref "C23") (pin "1") (pinfunction "1_1") (pintype "passive"))
      (node (ref "C24") (pin "1") (pinfunction "1_1") (pintype "passive"))
      (node (ref "C25") (pin "1") (pinfunction "1_1") (pintype "passive"))
      (node (ref "EXT") (pin "1") (pinfunction "1_1") (pintype "passive"))
      (node (ref "IC5") (pin "1") (pinfunction "PVCCL_1") (pintype "power_in"))
      (node (ref "IC5") (pin "10") (pinfunction "PVCCR_10") (pintype "power_in"))
      (node (ref "IC5") (pin "12") (pinfunction "PVCCR_12") (pintype "power_in"))
      (node (ref "IC5") (pin "19") (pinfunction "AVCC_19") (pintype "power_in"))
      (node (ref "IC5") (pin "20") (pinfunction "AVCC_20") (pintype "power_in"))
      (node (ref "IC5") (pin "3") (pinfunction "PVCCL_3") (pintype "power_in"))
      (node (ref "IC7") (pin "IN+") (pinfunction "VIN_IN+") (pintype "bidirectional"))
      (node (ref "R25") (pin "2") (pinfunction "2_2") (pintype "bidirectional"))
      (node (ref "T1") (pin "1") (pinfunction "D_1") (pintype "passive"))
      (node (ref "T1") (pin "2") (pinfunction "D_2") (pintype "passive"))
      (node (ref "T1") (pin "5") (pinfunction "D_5") (pintype "passive"))
      (node (ref "T1") (pin "6") (pinfunction "D_6") (pintype "passive"))
    )
    (net (code "62") (name "unconnected-(IC1-MISO{slash}PD6-Pad26)") (class "Default")
      (node (ref "IC1") (pin "26") (pinfunction "MISO/PD6_26") (pintype "bidirectional"))
    )
    (net (code "63") (name "unconnected-(IC1-OC0A{slash}PD0-Pad20)") (class "Default")
      (node (ref "IC1") (pin "20") (pinfunction "OC0A/PD0_20") (pintype "bidirectional"))
    )
    (net (code "64") (name "unconnected-(IC1-PA5{slash}ADCA5-Pad1)") (class "Default")
      (node (ref "IC1") (pin "1") (pinfunction "PA5/ADCA5_1") (pintype "bidirectional"))
    )
    (net (code "65") (name "unconnected-(IC1-PC1{slash}OC0B{slash}XCK0{slash}SCL-Pad11)") (class "Default")
      (node (ref "IC1") (pin "11") (pinfunction "PC1/OC0B/XCK0/SCL_11") (pintype "bidirectional"))
    )
    (net (code "66") (name "unconnected-(IC1-PC5{slash}OC1B{slash}MOSI-Pad15)") (class "Default")
      (node (ref "IC1") (pin "15") (pinfunction "PC5/OC1B/MOSI_15") (pintype "bidirectional"))
    )
    (net (code "67") (name "unconnected-(IC1-PC6{slash}MISO-Pad16)") (class "Default")
      (node (ref "IC1") (pin "16") (pinfunction "PC6/MISO_16") (pintype "bidirectional"))
    )
    (net (code "68") (name "unconnected-(IC1-PC7{slash}SCK-Pad17)") (class "Default")
      (node (ref "IC1") (pin "17") (pinfunction "PC7/SCK_17") (pintype "bidirectional"))
    )
    (net (code "69") (name "unconnected-(IC1-SCK{slash}PD7-Pad27)") (class "Default")
      (node (ref "IC1") (pin "27") (pinfunction "SCK/PD7_27") (pintype "bidirectional"))
    )
    (net (code "70") (name "unconnected-(IC1-SDA{slash}OC0A{slash}PE0-Pad28)") (class "Default")
      (node (ref "IC1") (pin "28") (pinfunction "SDA/OC0A/PE0_28") (pintype "bidirectional"))
    )
    (net (code "71") (name "unconnected-(IC1-XCK0{slash}OC0B{slash}PD1-Pad21)") (class "Default")
      (node (ref "IC1") (pin "21") (pinfunction "XCK0/OC0B/PD1_21") (pintype "bidirectional"))
    )
    (net (code "72") (name "unconnected-(IC1-\\S\\S{slash}PD4-Pad24)") (class "Default")
      (node (ref "IC1") (pin "24") (pinfunction "\\S\\S/PD4_24") (pintype "bidirectional"))
    )
    (net (code "73") (name "unconnected-(IC3-ADKEY1-Pad12)") (class "Default")
      (node (ref "IC3") (pin "12") (pinfunction "ADKEY1_12") (pintype "input"))
    )
    (net (code "74") (name "unconnected-(IC3-ADKEY2-Pad13)") (class "Default")
      (node (ref "IC3") (pin "13") (pinfunction "ADKEY2_13") (pintype "input"))
    )
    (net (code "75") (name "unconnected-(IC3-IO1-Pad9)") (class "Default")
      (node (ref "IC3") (pin "9") (pinfunction "IO1_9") (pintype "input"))
    )
    (net (code "76") (name "unconnected-(IC3-IO2-Pad11)") (class "Default")
      (node (ref "IC3") (pin "11") (pinfunction "IO2_11") (pintype "input"))
    )
    (net (code "77") (name "unconnected-(IC3-USB+-Pad14)") (class "Default")
      (node (ref "IC3") (pin "14") (pinfunction "USB+_14") (pintype "bidirectional"))
    )
    (net (code "78") (name "unconnected-(IC3-USB--Pad15)") (class "Default")
      (node (ref "IC3") (pin "15") (pinfunction "USB-_15") (pintype "bidirectional"))
    )
    (net (code "79") (name "unconnected-(IC6A-R2OUT-Pad9)") (class "Default")
      (node (ref "IC6") (pin "9") (pinfunction "R2OUT_9") (pintype "output"))
    )
    (net (code "80") (name "unconnected-(IC6A-T2OUT-Pad7)") (class "Default")
      (node (ref "IC6") (pin "7") (pinfunction "T2OUT_7") (pintype "output"))
    )
    (net (code "81") (name "unconnected-(PROG-NC-Pad3)") (class "Default")
      (node (ref "PROG") (pin "3") (pinfunction "NC_3") (pintype "passive"))
    )
    (net (code "82") (name "unconnected-(PROG-NC.-Pad4)") (class "Default")
      (node (ref "PROG") (pin "4") (pinfunction "NC._4") (pintype "passive"))
    )
  )
)
